# sqw23.net
KiCad netlist of a schematic drawn in EAGLE
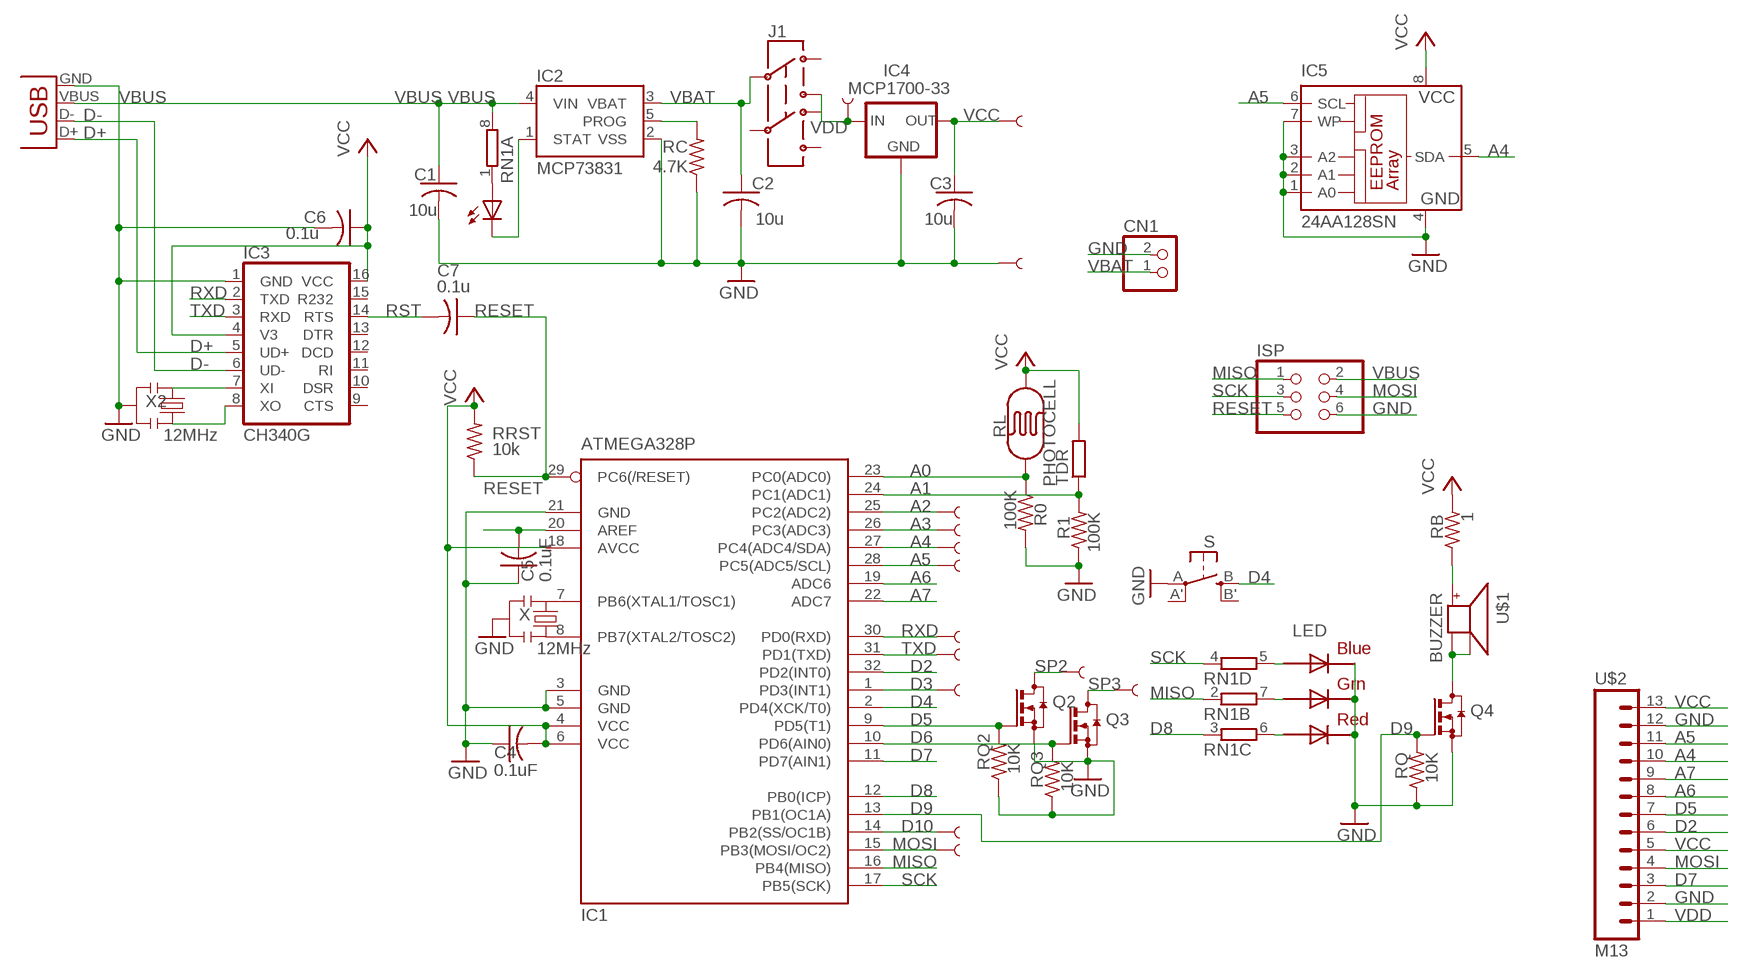
[diagram p0: schematic, sheet 1]

(export (version "E")
  (design (tool "Eeschema 10.0.6"))
  (components
    (comp (ref "C1")
      (value "10u")
      (footprint "eagle-import:C0805K")
      (libsource (lib "eagle-import") (part "adafruit2013_C-USC0805K"))
    )
    (comp (ref "C2")
      (value "10u")
      (footprint "eagle-import:C0805K")
      (libsource (lib "eagle-import") (part "adafruit2013_C-USC0805K"))
    )
    (comp (ref "C3")
      (value "10u")
      (footprint "eagle-import:C0805K")
      (libsource (lib "eagle-import") (part "adafruit2013_C-USC0805K"))
    )
    (comp (ref "C4")
      (value "0.1uF")
      (footprint "eagle-import:C0805K")
      (libsource (lib "eagle-import") (part "adafruit2013_C-USC0805K"))
    )
    (comp (ref "C5")
      (value "0.1uF")
      (footprint "eagle-import:C0805K")
      (libsource (lib "eagle-import") (part "adafruit2013_C-USC0805K"))
    )
    (comp (ref "C6")
      (value "0.1u")
      (footprint "eagle-import:C0805K")
      (libsource (lib "eagle-import") (part "C-USC0805K"))
    )
    (comp (ref "C7")
      (value "0.1u")
      (footprint "eagle-import:C0805K")
      (libsource (lib "eagle-import") (part "C-USC0805K"))
    )
    (comp (ref "CHG")
      (value "0805")
      (footprint "eagle-import:CHIPLED_0805")
      (libsource (lib "eagle-import") (part "LEDCHIPLED_0805"))
    )
    (comp (ref "CN1")
      (value "JST_2PIN-SMT-RA")
      (footprint "eagle-import:JST-PH-2-SMT-RA")
      (libsource (lib "eagle-import") (part "JST_2PIN-SMT-RA"))
    )
    (comp (ref "IC1")
      (value "ATMEGA328P")
      (footprint "eagle-import:TQFP32-08")
      (fields (field (name "MPN") "ATMEGA8-16AU"))
      (libsource (lib "eagle-import") (part "MEGA8-AI"))
    )
    (comp (ref "IC2")
      (value "MCP73831")
      (footprint "eagle-import:SOT23-5")
      (libsource (lib "eagle-import") (part "MCP73831"))
    )
    (comp (ref "IC3")
      (value "CH340G")
      (footprint "eagle-import:SO16")
      (libsource (lib "eagle-import") (part "CH340G"))
    )
    (comp (ref "IC4")
      (value "MCP1700-33")
      (footprint "eagle-import:SOT89")
      (libsource (lib "eagle-import") (part "MCP1700SOT89"))
    )
    (comp (ref "IC5")
      (value "24AA128SN")
      (footprint "eagle-import:SO-08")
      (fields (field (name "MF") "MICROCHIP") (field (name "MPN") "24AA128-I/SN"))
      (libsource (lib "eagle-import") (part "24SNAA128"))
    )
    (comp (ref "ISP")
      (value "PINHD-2X3")
      (footprint "eagle-import:2X03")
      (libsource (lib "eagle-import") (part "PINHD-2X3"))
    )
    (comp (ref "J1")
      (value "AYZ0202")
      (footprint "eagle-import:AYZ0202")
      (libsource (lib "eagle-import") (part "AYZ0202"))
    )
    (comp (ref "LED")
      (value "RGBLED5050")
      (footprint "eagle-import:RGBLED5050")
      (libsource (lib "eagle-import") (part "RGBLED5050"))
    )
    (comp (ref "PAD_3")
      (value "SEWTAP6")
      (footprint "eagle-import:PETAL-SMALL-2SIDE11")
      (libsource (lib "eagle-import") (part "SEWTAP611"))
    )
    (comp (ref "PAD_5")
      (value "SEWTAP6")
      (footprint "eagle-import:PETAL-SMALL-2SIDE1")
      (libsource (lib "eagle-import") (part "SEWTAP61"))
    )
    (comp (ref "PAD_6")
      (value "SEWTAP6")
      (footprint "eagle-import:PETAL-SMALL-2SIDE1")
      (libsource (lib "eagle-import") (part "SEWTAP61"))
    )
    (comp (ref "PAD_10")
      (value "SEWTAP6")
      (footprint "eagle-import:PETAL-SMALL-2SIDE11")
      (libsource (lib "eagle-import") (part "SEWTAP611"))
    )
    (comp (ref "PAD_11")
      (value "SEWTAP6")
      (footprint "eagle-import:PETAL-SMALL-2SIDE1")
      (libsource (lib "eagle-import") (part "SEWTAP61"))
    )
    (comp (ref "PAD_A2")
      (value "SEWTAP6")
      (footprint "eagle-import:PETAL-SMALL-2SIDE1")
      (libsource (lib "eagle-import") (part "SEWTAP61"))
    )
    (comp (ref "PAD_A3")
      (value "SEWTAP6")
      (footprint "eagle-import:PETAL-SMALL-2SIDE1")
      (libsource (lib "eagle-import") (part "SEWTAP61"))
    )
    (comp (ref "PAD_A4")
      (value "SEWTAP6")
      (footprint "eagle-import:PETAL-SMALL-2SIDE11")
      (libsource (lib "eagle-import") (part "SEWTAP611"))
    )
    (comp (ref "PAD_A5")
      (value "SEWTAP6")
      (footprint "eagle-import:PETAL-SMALL-2SIDE11")
      (libsource (lib "eagle-import") (part "SEWTAP611"))
    )
    (comp (ref "PAD_GND")
      (value "SEWTAP6")
      (footprint "eagle-import:PETAL-SMALL-2SIDE11")
      (libsource (lib "eagle-import") (part "SEWTAP611"))
    )
    (comp (ref "PAD_RXD")
      (value "SEWTAP61")
      (footprint "eagle-import:PETAL-SMALL-2SIDE1")
      (libsource (lib "eagle-import") (part "SEWTAP61"))
    )
    (comp (ref "PAD_TXD")
      (value "SEWTAP6")
      (footprint "eagle-import:PETAL-SMALL-2SIDE1")
      (libsource (lib "eagle-import") (part "SEWTAP61"))
    )
    (comp (ref "PAD_VBAT")
      (value "SEWTAP6")
      (footprint "eagle-import:PETAL-SMALL-2SIDE1")
      (libsource (lib "eagle-import") (part "SEWTAP61"))
    )
    (comp (ref "PAD_VCC")
      (value "SEWTAP6")
      (footprint "eagle-import:PETAL-SMALL-2SIDE11")
      (libsource (lib "eagle-import") (part "SEWTAP611"))
    )
    (comp (ref "Q2")
      (value "BSS123")
      (footprint "eagle-import:SOT23")
      (libsource (lib "eagle-import") (part "BSS123"))
    )
    (comp (ref "Q3")
      (value "BSS123")
      (footprint "eagle-import:SOT23")
      (libsource (lib "eagle-import") (part "BSS123"))
    )
    (comp (ref "Q4")
      (value "BSS123")
      (footprint "eagle-import:SOT23")
      (libsource (lib "eagle-import") (part "BSS123"))
    )
    (comp (ref "R0")
      (value "100K")
      (footprint "eagle-import:R0805")
      (libsource (lib "eagle-import") (part "R-US_R0805"))
    )
    (comp (ref "R1")
      (value "100K")
      (footprint "eagle-import:R0805")
      (libsource (lib "eagle-import") (part "R-US_R0805"))
    )
    (comp (ref "RB")
      (value "1")
      (footprint "eagle-import:R0805")
      (libsource (lib "eagle-import") (part "R-US_R0805"))
    )
    (comp (ref "RC")
      (value "4.7K")
      (footprint "eagle-import:R0805")
      (libsource (lib "eagle-import") (part "R-US_R0805"))
    )
    (comp (ref "RL")
      (value "PHOTOCELL")
      (footprint "eagle-import:PHOTOCELL")
      (libsource (lib "eagle-import") (part "PHOTOCELLPTH"))
    )
    (comp (ref "RN1")
      (value "4R-NEXB38V")
      (footprint "eagle-import:EXB38V")
      (libsource (lib "eagle-import") (part "4R-NEXB38V"))
    )
    (comp (ref "RQ")
      (value "10K")
      (footprint "eagle-import:R0805")
      (libsource (lib "eagle-import") (part "R-US_R0805"))
    )
    (comp (ref "RQ2")
      (value "10K")
      (footprint "eagle-import:R0805")
      (libsource (lib "eagle-import") (part "R-US_R0805"))
    )
    (comp (ref "RQ3")
      (value "10K")
      (footprint "eagle-import:R0805")
      (libsource (lib "eagle-import") (part "R-US_R0805"))
    )
    (comp (ref "RRST")
      (value "10k")
      (footprint "eagle-import:R0805")
      (libsource (lib "eagle-import") (part "R-US_R0805"))
    )
    (comp (ref "S")
      (value "EVQQ2")
      (footprint "eagle-import:EVQ-Q2")
      (libsource (lib "eagle-import") (part "EVQQ2"))
    )
    (comp (ref "TDR")
      (value "R-EU_V526-0")
      (footprint "eagle-import:V526-0")
      (libsource (lib "eagle-import") (part "R-EU_V526-0"))
    )
    (comp (ref "U$1")
      (value "BUZZER")
      (footprint "eagle-import:SMT-8585-BUZZER")
      (libsource (lib "eagle-import") (part "BUZZER"))
    )
    (comp (ref "U$2")
      (value "M13")
      (footprint "eagle-import:1X13")
      (libsource (lib "eagle-import") (part "M13"))
    )
    (comp (ref "X")
      (value "12MHz")
      (footprint "eagle-import:RESONATOR-SMD")
      (libsource (lib "eagle-import") (part "RESONATORSMD"))
    )
    (comp (ref "X1")
      (value "USBSMD")
      (footprint "eagle-import:USB-MINIB")
      (libsource (lib "eagle-import") (part "USBSMD"))
    )
    (comp (ref "X2")
      (value "12MHz")
      (footprint "eagle-import:RESONATOR-SMD")
      (libsource (lib "eagle-import") (part "RESONATORSMD"))
    )
  )
  (nets
    (net (code "1") (name "/A0") (class "Default")
      (node (ref "IC1") (pin "23") (pinfunction "PC0(ADC0)_23") (pintype "bidirectional"))
      (node (ref "R0") (pin "1") (pinfunction "1_1") (pintype "passive"))
      (node (ref "RL") (pin "1") (pinfunction "P$1_1") (pintype "bidirectional"))
    )
    (net (code "2") (name "/A1") (class "Default")
      (node (ref "IC1") (pin "24") (pinfunction "PC1(ADC1)_24") (pintype "bidirectional"))
      (node (ref "R1") (pin "2") (pinfunction "2_2") (pintype "passive"))
      (node (ref "TDR") (pin "1") (pinfunction "1_1") (pintype "passive"))
    )
    (net (code "3") (name "/A2") (class "Default")
      (node (ref "IC1") (pin "25") (pinfunction "PC2(ADC2)_25") (pintype "bidirectional"))
      (node (ref "PAD_A2") (pin "1") (pinfunction "1_1") (pintype "bidirectional"))
    )
    (net (code "4") (name "/A3") (class "Default")
      (node (ref "IC1") (pin "26") (pinfunction "PC3(ADC3)_26") (pintype "bidirectional"))
      (node (ref "PAD_A3") (pin "1") (pinfunction "1_1") (pintype "bidirectional"))
    )
    (net (code "5") (name "/A4") (class "Default")
      (node (ref "IC1") (pin "27") (pinfunction "PC4(ADC4/SDA)_27") (pintype "bidirectional"))
      (node (ref "IC5") (pin "5") (pinfunction "SDA_5") (pintype "bidirectional"))
      (node (ref "PAD_A4") (pin "1") (pinfunction "1_1") (pintype "bidirectional"))
      (node (ref "U$2") (pin "10") (pinfunction "10_10") (pintype "passive"))
    )
    (net (code "6") (name "/A5") (class "Default")
      (node (ref "IC1") (pin "28") (pinfunction "PC5(ADC5/SCL)_28") (pintype "bidirectional"))
      (node (ref "IC5") (pin "6") (pinfunction "SCL_6") (pintype "input"))
      (node (ref "PAD_A5") (pin "1") (pinfunction "1_1") (pintype "bidirectional"))
      (node (ref "U$2") (pin "11") (pinfunction "11_11") (pintype "passive"))
    )
    (net (code "7") (name "/A6") (class "Default")
      (node (ref "IC1") (pin "19") (pinfunction "ADC6_19") (pintype "bidirectional"))
      (node (ref "U$2") (pin "8") (pinfunction "8_8") (pintype "passive"))
    )
    (net (code "8") (name "/A7") (class "Default")
      (node (ref "IC1") (pin "22") (pinfunction "ADC7_22") (pintype "bidirectional"))
      (node (ref "U$2") (pin "9") (pinfunction "9_9") (pintype "passive"))
    )
    (net (code "9") (name "/D+") (class "Default")
      (node (ref "IC3") (pin "5") (pinfunction "UD+_5") (pintype "bidirectional"))
      (node (ref "X1") (pin "D+") (pinfunction "D+_D+") (pintype "bidirectional"))
    )
    (net (code "10") (name "/D-") (class "Default")
      (node (ref "IC3") (pin "6") (pinfunction "UD-_6") (pintype "bidirectional"))
      (node (ref "X1") (pin "D-") (pinfunction "D-_D-") (pintype "bidirectional"))
    )
    (net (code "11") (name "/D2") (class "Default")
      (node (ref "IC1") (pin "32") (pinfunction "PD2(INT0)_32") (pintype "bidirectional"))
      (node (ref "U$2") (pin "6") (pinfunction "6_6") (pintype "passive"))
    )
    (net (code "12") (name "/D3") (class "Default")
      (node (ref "IC1") (pin "1") (pinfunction "PD3(INT1)_1") (pintype "bidirectional"))
      (node (ref "PAD_3") (pin "1") (pinfunction "1_1") (pintype "bidirectional"))
    )
    (net (code "13") (name "/D4") (class "Default")
      (node (ref "IC1") (pin "2") (pinfunction "PD4(XCK/T0)_2") (pintype "bidirectional"))
      (node (ref "S") (pin "B") (pinfunction "S_B") (pintype "passive"))
    )
    (net (code "14") (name "/D5") (class "Default")
      (node (ref "IC1") (pin "9") (pinfunction "PD5(T1)_9") (pintype "bidirectional"))
      (node (ref "Q2") (pin "1") (pinfunction "G_1") (pintype "passive"))
      (node (ref "RQ2") (pin "2") (pinfunction "2_2") (pintype "passive"))
      (node (ref "U$2") (pin "7") (pinfunction "7_7") (pintype "passive"))
    )
    (net (code "15") (name "/D6") (class "Default")
      (node (ref "IC1") (pin "10") (pinfunction "PD6(AIN0)_10") (pintype "bidirectional"))
      (node (ref "Q3") (pin "1") (pinfunction "G_1") (pintype "passive"))
      (node (ref "RQ3") (pin "2") (pinfunction "2_2") (pintype "passive"))
    )
    (net (code "16") (name "/D7") (class "Default")
      (node (ref "IC1") (pin "11") (pinfunction "PD7(AIN1)_11") (pintype "bidirectional"))
      (node (ref "U$2") (pin "3") (pinfunction "3_3") (pintype "passive"))
    )
    (net (code "17") (name "/D8") (class "Default")
      (node (ref "IC1") (pin "12") (pinfunction "PB0(ICP)_12") (pintype "bidirectional"))
      (node (ref "RN1") (pin "3") (pinfunction "1_3") (pintype "passive"))
    )
    (net (code "18") (name "/D9") (class "Default")
      (node (ref "IC1") (pin "13") (pinfunction "PB1(OC1A)_13") (pintype "bidirectional"))
      (node (ref "Q4") (pin "1") (pinfunction "G_1") (pintype "passive"))
      (node (ref "RQ") (pin "2") (pinfunction "2_2") (pintype "passive"))
    )
    (net (code "19") (name "/D10") (class "Default")
      (node (ref "IC1") (pin "14") (pinfunction "PB2(SS/OC1B)_14") (pintype "bidirectional"))
      (node (ref "PAD_10") (pin "1") (pinfunction "1_1") (pintype "bidirectional"))
    )
    (net (code "20") (name "/MISO") (class "Default")
      (node (ref "IC1") (pin "16") (pinfunction "PB4(MISO)_16") (pintype "bidirectional"))
      (node (ref "ISP") (pin "1") (pinfunction "1_1") (pintype "passive"))
      (node (ref "RN1") (pin "2") (pinfunction "1_2") (pintype "passive"))
    )
    (net (code "21") (name "/MOSI") (class "Default")
      (node (ref "IC1") (pin "15") (pinfunction "PB3(MOSI/OC2)_15") (pintype "bidirectional"))
      (node (ref "ISP") (pin "4") (pinfunction "4_4") (pintype "passive"))
      (node (ref "PAD_11") (pin "1") (pinfunction "1_1") (pintype "bidirectional"))
      (node (ref "U$2") (pin "4") (pinfunction "4_4") (pintype "passive"))
    )
    (net (code "22") (name "/RESET") (class "Default")
      (node (ref "C7") (pin "1") (pinfunction "1_1") (pintype "passive"))
      (node (ref "IC1") (pin "29") (pinfunction "PC6(/RESET)_29") (pintype "bidirectional"))
      (node (ref "ISP") (pin "5") (pinfunction "5_5") (pintype "passive"))
      (node (ref "RRST") (pin "1") (pinfunction "1_1") (pintype "passive"))
    )
    (net (code "23") (name "/RST") (class "Default")
      (node (ref "C7") (pin "2") (pinfunction "2_2") (pintype "passive"))
      (node (ref "IC3") (pin "14") (pinfunction "RTS_14") (pintype "bidirectional"))
    )
    (net (code "24") (name "/RXD") (class "Default")
      (node (ref "IC1") (pin "30") (pinfunction "PD0(RXD)_30") (pintype "bidirectional"))
      (node (ref "IC3") (pin "2") (pinfunction "TXD_2") (pintype "bidirectional"))
      (node (ref "PAD_RXD") (pin "1") (pinfunction "1_1") (pintype "bidirectional"))
    )
    (net (code "25") (name "/SCK") (class "Default")
      (node (ref "IC1") (pin "17") (pinfunction "PB5(SCK)_17") (pintype "bidirectional"))
      (node (ref "ISP") (pin "3") (pinfunction "3_3") (pintype "passive"))
      (node (ref "RN1") (pin "4") (pinfunction "1_4") (pintype "passive"))
    )
    (net (code "26") (name "/SP2") (class "Default")
      (node (ref "PAD_5") (pin "1") (pinfunction "1_1") (pintype "bidirectional"))
      (node (ref "Q2") (pin "3") (pinfunction "D_3") (pintype "passive"))
    )
    (net (code "27") (name "/SP3") (class "Default")
      (node (ref "PAD_6") (pin "1") (pinfunction "1_1") (pintype "bidirectional"))
      (node (ref "Q3") (pin "3") (pinfunction "D_3") (pintype "passive"))
    )
    (net (code "28") (name "/TXD") (class "Default")
      (node (ref "IC1") (pin "31") (pinfunction "PD1(TXD)_31") (pintype "bidirectional"))
      (node (ref "IC3") (pin "3") (pinfunction "RXD_3") (pintype "bidirectional"))
      (node (ref "PAD_TXD") (pin "1") (pinfunction "1_1") (pintype "bidirectional"))
    )
    (net (code "29") (name "/VBAT") (class "Default")
      (node (ref "C2") (pin "1") (pinfunction "1_1") (pintype "passive"))
      (node (ref "CN1") (pin "1") (pinfunction "2_1") (pintype "passive"))
      (node (ref "IC2") (pin "3") (pinfunction "VBAT_3") (pintype "power_in"))
      (node (ref "J1") (pin "2") (pinfunction "2_2") (pintype "bidirectional"))
    )
    (net (code "30") (name "/VBUS") (class "Default")
      (node (ref "C1") (pin "1") (pinfunction "1_1") (pintype "passive"))
      (node (ref "IC2") (pin "4") (pinfunction "VIN_4") (pintype "power_in"))
      (node (ref "ISP") (pin "2") (pinfunction "2_2") (pintype "passive"))
      (node (ref "RN1") (pin "8") (pinfunction "2_8") (pintype "passive"))
      (node (ref "X1") (pin "VBUS") (pinfunction "VBUS_VBUS") (pintype "bidirectional"))
    )
    (net (code "31") (name "/VDD") (class "Default")
      (node (ref "IC4") (pin "2") (pinfunction "IN_2") (pintype "input"))
      (node (ref "J1") (pin "1") (pinfunction "3_1") (pintype "bidirectional"))
      (node (ref "PAD_VBAT") (pin "1") (pinfunction "1_1") (pintype "bidirectional"))
      (node (ref "U$2") (pin "1") (pinfunction "1_1") (pintype "passive"))
    )
    (net (code "32") (name "GND") (class "Default")
      (node (ref "C1") (pin "2") (pinfunction "2_2") (pintype "passive"))
      (node (ref "C2") (pin "2") (pinfunction "2_2") (pintype "passive"))
      (node (ref "C3") (pin "2") (pinfunction "2_2") (pintype "passive"))
      (node (ref "C4") (pin "1") (pinfunction "1_1") (pintype "passive"))
      (node (ref "C5") (pin "1") (pinfunction "1_1") (pintype "passive"))
      (node (ref "C6") (pin "2") (pinfunction "2_2") (pintype "passive"))
      (node (ref "CN1") (pin "2") (pinfunction "1_2") (pintype "passive"))
      (node (ref "IC1") (pin "21") (pinfunction "GND_21") (pintype "power_in"))
      (node (ref "IC1") (pin "3") (pinfunction "GND_3") (pintype "power_in"))
      (node (ref "IC1") (pin "5") (pinfunction "GND_5") (pintype "power_in"))
      (node (ref "IC2") (pin "2") (pinfunction "VSS_2") (pintype "power_in"))
      (node (ref "IC3") (pin "1") (pinfunction "GND_1") (pintype "power_in"))
      (node (ref "IC4") (pin "1") (pinfunction "GND_1") (pintype "input"))
      (node (ref "IC5") (pin "1") (pinfunction "A0_1") (pintype "input"))
      (node (ref "IC5") (pin "2") (pinfunction "A1_2") (pintype "input"))
      (node (ref "IC5") (pin "3") (pinfunction "A2_3") (pintype "input"))
      (node (ref "IC5") (pin "4") (pinfunction "GND_4") (pintype "power_in"))
      (node (ref "IC5") (pin "7") (pinfunction "WP_7") (pintype "input"))
      (node (ref "ISP") (pin "6") (pinfunction "6_6") (pintype "passive"))
      (node (ref "LED") (pin "4") (pinfunction "BLUE_C_4") (pintype "bidirectional"))
      (node (ref "LED") (pin "5") (pinfunction "RED_C_5") (pintype "bidirectional"))
      (node (ref "LED") (pin "6") (pinfunction "GREEN_C_6") (pintype "bidirectional"))
      (node (ref "PAD_GND") (pin "1") (pinfunction "1_1") (pintype "bidirectional"))
      (node (ref "Q2") (pin "2") (pinfunction "S_2") (pintype "passive"))
      (node (ref "Q3") (pin "2") (pinfunction "S_2") (pintype "passive"))
      (node (ref "Q4") (pin "2") (pinfunction "S_2") (pintype "passive"))
      (node (ref "R0") (pin "2") (pinfunction "2_2") (pintype "passive"))
      (node (ref "R1") (pin "1") (pinfunction "1_1") (pintype "passive"))
      (node (ref "RC") (pin "1") (pinfunction "1_1") (pintype "passive"))
      (node (ref "RQ") (pin "1") (pinfunction "1_1") (pintype "passive"))
      (node (ref "RQ2") (pin "1") (pinfunction "1_1") (pintype "passive"))
      (node (ref "RQ3") (pin "1") (pinfunction "1_1") (pintype "passive"))
      (node (ref "S") (pin "A") (pinfunction "P_A") (pintype "passive"))
      (node (ref "U$2") (pin "12") (pinfunction "12_12") (pintype "passive"))
      (node (ref "U$2") (pin "2") (pinfunction "2_2") (pintype "passive"))
      (node (ref "X") (pin "2") (pinfunction "2_2") (pintype "passive"))
      (node (ref "X1") (pin "GND") (pinfunction "GND_GND") (pintype "bidirectional"))
      (node (ref "X2") (pin "2") (pinfunction "2_2") (pintype "passive"))
    )
    (net (code "33") (name "Net-(CHG-PadA)") (class "Default")
      (node (ref "CHG") (pin "A") (pinfunction "A_A") (pintype "passive"))
      (node (ref "RN1") (pin "1") (pinfunction "1_1") (pintype "passive"))
    )
    (net (code "34") (name "Net-(IC1-AREF)") (class "Default")
      (node (ref "C5") (pin "2") (pinfunction "2_2") (pintype "passive"))
      (node (ref "IC1") (pin "20") (pinfunction "AREF_20") (pintype "passive"))
    )
    (net (code "35") (name "Net-(IC1-PB6(XTAL1{slash}TOSC1))") (class "Default")
      (node (ref "IC1") (pin "7") (pinfunction "PB6(XTAL1/TOSC1)_7") (pintype "bidirectional"))
      (node (ref "X") (pin "1") (pinfunction "1_1") (pintype "passive"))
    )
    (net (code "36") (name "Net-(IC1-PB7(XTAL2{slash}TOSC2))") (class "Default")
      (node (ref "IC1") (pin "8") (pinfunction "PB7(XTAL2/TOSC2)_8") (pintype "bidirectional"))
      (node (ref "X") (pin "3") (pinfunction "3_3") (pintype "passive"))
    )
    (net (code "37") (name "Net-(IC2-PROG)") (class "Default")
      (node (ref "IC2") (pin "5") (pinfunction "PROG_5") (pintype "input"))
      (node (ref "RC") (pin "2") (pinfunction "2_2") (pintype "passive"))
    )
    (net (code "38") (name "Net-(IC2-STAT)") (class "Default")
      (node (ref "CHG") (pin "C") (pinfunction "C_C") (pintype "passive"))
      (node (ref "IC2") (pin "1") (pinfunction "STAT_1") (pintype "output"))
    )
    (net (code "39") (name "Net-(IC3-XI)") (class "Default")
      (node (ref "IC3") (pin "7") (pinfunction "XI_7") (pintype "bidirectional"))
      (node (ref "X2") (pin "1") (pinfunction "1_1") (pintype "passive"))
    )
    (net (code "40") (name "Net-(IC3-XO)") (class "Default")
      (node (ref "IC3") (pin "8") (pinfunction "XO_8") (pintype "bidirectional"))
      (node (ref "X2") (pin "3") (pinfunction "3_3") (pintype "passive"))
    )
    (net (code "41") (name "Net-(LED-BLUE_A)") (class "Default")
      (node (ref "LED") (pin "3") (pinfunction "BLUE_A_3") (pintype "bidirectional"))
      (node (ref "RN1") (pin "5") (pinfunction "2_5") (pintype "passive"))
    )
    (net (code "42") (name "Net-(LED-GREEN_A)") (class "Default")
      (node (ref "LED") (pin "1") (pinfunction "GREEN_A_1") (pintype "bidirectional"))
      (node (ref "RN1") (pin "7") (pinfunction "2_7") (pintype "passive"))
    )
    (net (code "43") (name "Net-(LED-RED_A)") (class "Default")
      (node (ref "LED") (pin "2") (pinfunction "RED_A_2") (pintype "bidirectional"))
      (node (ref "RN1") (pin "6") (pinfunction "2_6") (pintype "passive"))
    )
    (net (code "44") (name "Net-(Q4-D)") (class "Default")
      (node (ref "Q4") (pin "3") (pinfunction "D_3") (pintype "passive"))
      (node (ref "U$1") (pin "-") (pinfunction "-_-") (pintype "passive"))
      (node (ref "U$1") (pin "A-") (pinfunction "A-_A-") (pintype "passive"))
    )
    (net (code "45") (name "Net-(RB-Pad1)") (class "Default")
      (node (ref "RB") (pin "1") (pinfunction "1_1") (pintype "passive"))
      (node (ref "U$1") (pin "+") (pinfunction "+_+") (pintype "passive"))
    )
    (net (code "46") (name "VCC") (class "Default")
      (node (ref "C3") (pin "1") (pinfunction "1_1") (pintype "passive"))
      (node (ref "C4") (pin "2") (pinfunction "2_2") (pintype "passive"))
      (node (ref "C6") (pin "1") (pinfunction "1_1") (pintype "passive"))
      (node (ref "IC1") (pin "18") (pinfunction "AVCC_18") (pintype "power_in"))
      (node (ref "IC1") (pin "4") (pinfunction "VCC_4") (pintype "power_in"))
      (node (ref "IC1") (pin "6") (pinfunction "VCC_6") (pintype "power_in"))
      (node (ref "IC3") (pin "16") (pinfunction "VCC_16") (pintype "power_in"))
      (node (ref "IC3") (pin "4") (pinfunction "V3_4") (pintype "bidirectional"))
      (node (ref "IC4") (pin "3") (pinfunction "OUT_3") (pintype "passive"))
      (node (ref "IC5") (pin "8") (pinfunction "VCC_8") (pintype "power_in"))
      (node (ref "PAD_VCC") (pin "1") (pinfunction "1_1") (pintype "bidirectional"))
      (node (ref "RB") (pin "2") (pinfunction "2_2") (pintype "passive"))
      (node (ref "RL") (pin "2") (pinfunction "P$2_2") (pintype "bidirectional"))
      (node (ref "RRST") (pin "2") (pinfunction "2_2") (pintype "passive"))
      (node (ref "TDR") (pin "2") (pinfunction "2_2") (pintype "passive"))
      (node (ref "U$2") (pin "13") (pinfunction "13_13") (pintype "passive"))
      (node (ref "U$2") (pin "5") (pinfunction "5_5") (pintype "passive"))
    )
    (net (code "47") (name "unconnected-(IC3-CTS-Pad9)") (class "Default")
      (node (ref "IC3") (pin "9") (pinfunction "CTS_9") (pintype "bidirectional"))
    )
    (net (code "48") (name "unconnected-(IC3-DCD-Pad12)") (class "Default")
      (node (ref "IC3") (pin "12") (pinfunction "DCD_12") (pintype "bidirectional"))
    )
    (net (code "49") (name "unconnected-(IC3-DSR-Pad10)") (class "Default")
      (node (ref "IC3") (pin "10") (pinfunction "DSR_10") (pintype "bidirectional"))
    )
    (net (code "50") (name "unconnected-(IC3-DTR-Pad13)") (class "Default")
      (node (ref "IC3") (pin "13") (pinfunction "DTR_13") (pintype "bidirectional"))
    )
    (net (code "51") (name "unconnected-(IC3-R232-Pad15)") (class "Default")
      (node (ref "IC3") (pin "15") (pinfunction "R232_15") (pintype "bidirectional"))
    )
    (net (code "52") (name "unconnected-(IC3-RI-Pad11)") (class "Default")
      (node (ref "IC3") (pin "11") (pinfunction "RI_11") (pintype "bidirectional"))
    )
    (net (code "53") (name "unconnected-(J1-1-Pad3)") (class "Default")
      (node (ref "J1") (pin "3") (pinfunction "1_3") (pintype "bidirectional"))
    )
    (net (code "54") (name "unconnected-(J1-4-Pad6)") (class "Default")
      (node (ref "J1") (pin "6") (pinfunction "4_6") (pintype "bidirectional"))
    )
    (net (code "55") (name "unconnected-(J1-6-Pad4)") (class "Default")
      (node (ref "J1") (pin "4") (pinfunction "6_4") (pintype "bidirectional"))
    )
    (net (code "56") (name "unconnected-(J1-Pad5)") (class "Default")
      (node (ref "J1") (pin "5") (pinfunction "5_5") (pintype "bidirectional"))
    )
    (net (code "57") (name "unconnected-(S-P1-PadA')") (class "Default")
      (node (ref "S") (pin "A'") (pinfunction "P1_A'") (pintype "passive"))
    )
    (net (code "58") (name "unconnected-(S-S1-PadB')") (class "Default")
      (node (ref "S") (pin "B'") (pinfunction "S1_B'") (pintype "passive"))
    )
  )
)
